# SML-230109PCB1__BLE.net
KiCad netlist of a schematic drawn in Altium Designer
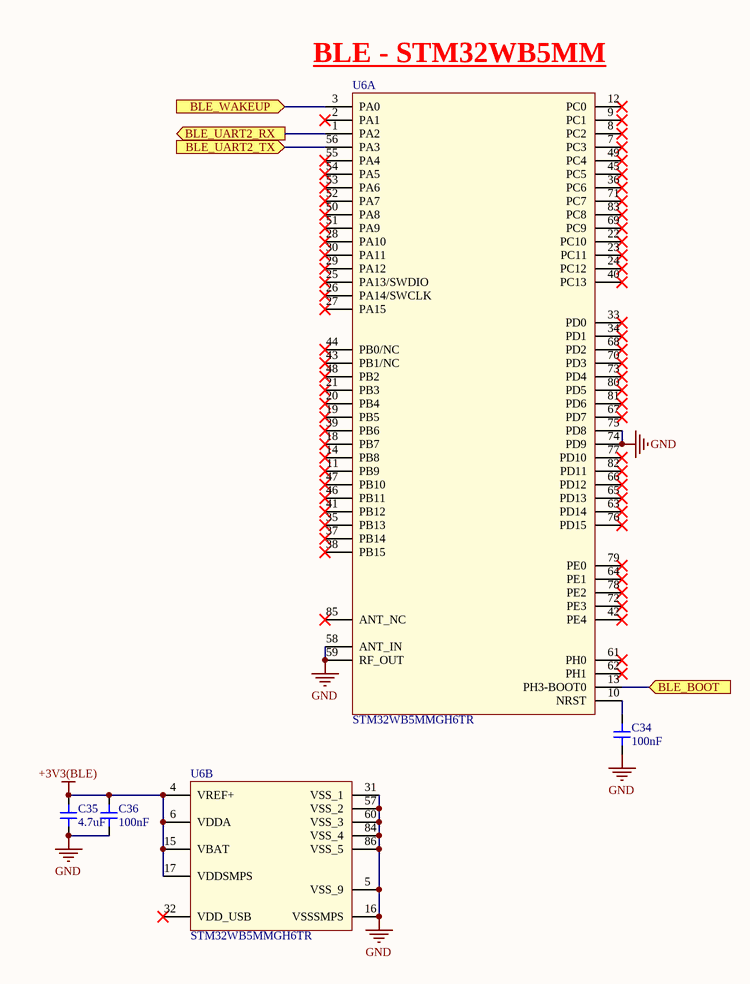
[diagram p0: SML-230109PCB1__BLE.SchDoc]

(export (version "E")
  (design (tool "Eeschema 10.0.6"))
  (components
    (comp (ref "C34")
      (value "100nF")
      (footprint "[G] CAP-MLCC__0603")
      (description "CAP MLCC 0603")
      (fields (field (name "VOLTAGE") "010") (field (name "Comment") "."))
      (libsource (lib "DEB_LIB_SCH_22-03") (part "CAP_MLCC_0603"))
    )
    (comp (ref "C35")
      (value "4.7uF")
      (footprint "[G] CAP-MLCC__0603")
      (description "CAP MLCC 0603")
      (fields (field (name "VOLTAGE") "010") (field (name "Comment") "."))
      (libsource (lib "DEB_LIB_SCH_22-03") (part "CAP_MLCC_0603"))
    )
    (comp (ref "C36")
      (value "100nF")
      (footprint "[G] CAP-MLCC__0603")
      (description "CAP MLCC 0603")
      (fields (field (name "VOLTAGE") "010") (field (name "Comment") "."))
      (libsource (lib "DEB_LIB_SCH_22-03") (part "CAP_MLCC_0603"))
    )
    (comp (ref "U6")
      (value ".")
      (footprint "MCU/BLE__STM32WB5MMG__SIP-LGA-86")
      (description "MCU/BLE ARM 32bit, M0+ & M4 (64MHz), 1MB/256KB, 6dBm, -96dBm, SIP-LGA-86")
      (fields (field (name "[01] - MPN CODE") "STM32WB5MMGH6TR"))
      (libsource (lib "DEB_LIB_SCH_22-03") (part "STM32WB5MMGH6TR"))
    )
  )
  (nets
    (net (code "1") (name "+3V3(BLE)") (class "Default")
      (node (ref "C35") (pin "2") (pinfunction "2_2") (pintype "passive"))
      (node (ref "C36") (pin "2") (pinfunction "2_2") (pintype "passive"))
      (node (ref "U6") (pin "15") (pinfunction "VBAT_15") (pintype "passive"))
      (node (ref "U6") (pin "17") (pinfunction "VDDSMPS_17") (pintype "passive"))
      (node (ref "U6") (pin "4") (pinfunction "VREF+_4") (pintype "passive"))
      (node (ref "U6") (pin "6") (pinfunction "VDDA_6") (pintype "passive"))
    )
    (net (code "2") (name "/BLE_BOOT") (class "Default")
      (node (ref "U6") (pin "13") (pinfunction "PH3-BOOT0_13") (pintype "passive"))
    )
    (net (code "3") (name "/BLE_UART2_RX") (class "Default")
      (node (ref "U6") (pin "1") (pinfunction "PA2_1") (pintype "passive"))
    )
    (net (code "4") (name "/BLE_UART2_TX") (class "Default")
      (node (ref "U6") (pin "56") (pinfunction "PA3_56") (pintype "passive"))
    )
    (net (code "5") (name "/BLE_WAKEUP") (class "Default")
      (node (ref "U6") (pin "3") (pinfunction "PA0_3") (pintype "passive"))
    )
    (net (code "6") (name "GND") (class "Default")
      (node (ref "C34") (pin "1") (pinfunction "1_1") (pintype "passive"))
      (node (ref "C35") (pin "1") (pinfunction "1_1") (pintype "passive"))
      (node (ref "C36") (pin "1") (pinfunction "1_1") (pintype "passive"))
      (node (ref "U6") (pin "16") (pinfunction "VSSSMPS_16") (pintype "passive"))
      (node (ref "U6") (pin "31") (pinfunction "VSS_1_31") (pintype "passive"))
      (node (ref "U6") (pin "5") (pinfunction "VSS_9_5") (pintype "passive"))
      (node (ref "U6") (pin "57") (pinfunction "VSS_2_57") (pintype "passive"))
      (node (ref "U6") (pin "58") (pinfunction "ANT_IN_58") (pintype "passive"))
      (node (ref "U6") (pin "59") (pinfunction "RF_OUT_59") (pintype "passive"))
      (node (ref "U6") (pin "60") (pinfunction "VSS_3_60") (pintype "passive"))
      (node (ref "U6") (pin "74") (pinfunction "PD9_74") (pintype "passive"))
      (node (ref "U6") (pin "75") (pinfunction "PD8_75") (pintype "passive"))
      (node (ref "U6") (pin "84") (pinfunction "VSS_4_84") (pintype "passive"))
      (node (ref "U6") (pin "86") (pinfunction "VSS_5_86") (pintype "passive"))
    )
    (net (code "7") (name "Net-(U6A-NRST)") (class "Default")
      (node (ref "C34") (pin "2") (pinfunction "2_2") (pintype "passive"))
      (node (ref "U6") (pin "10") (pinfunction "NRST_10") (pintype "passive"))
    )
    (net (code "8") (name "unconnected-(U6A-ANT_NC-Pad85)") (class "Default")
      (node (ref "U6") (pin "85") (pinfunction "ANT_NC_85") (pintype "passive+no_connect"))
    )
    (net (code "9") (name "unconnected-(U6A-PA1-Pad2)") (class "Default")
      (node (ref "U6") (pin "2") (pinfunction "PA1_2") (pintype "passive+no_connect"))
    )
    (net (code "10") (name "unconnected-(U6A-PA4-Pad55)") (class "Default")
      (node (ref "U6") (pin "55") (pinfunction "PA4_55") (pintype "passive+no_connect"))
    )
    (net (code "11") (name "unconnected-(U6A-PA5-Pad54)") (class "Default")
      (node (ref "U6") (pin "54") (pinfunction "PA5_54") (pintype "passive+no_connect"))
    )
    (net (code "12") (name "unconnected-(U6A-PA6-Pad53)") (class "Default")
      (node (ref "U6") (pin "53") (pinfunction "PA6_53") (pintype "passive+no_connect"))
    )
    (net (code "13") (name "unconnected-(U6A-PA7-Pad52)") (class "Default")
      (node (ref "U6") (pin "52") (pinfunction "PA7_52") (pintype "passive+no_connect"))
    )
    (net (code "14") (name "unconnected-(U6A-PA8-Pad50)") (class "Default")
      (node (ref "U6") (pin "50") (pinfunction "PA8_50") (pintype "passive+no_connect"))
    )
    (net (code "15") (name "unconnected-(U6A-PA9-Pad51)") (class "Default")
      (node (ref "U6") (pin "51") (pinfunction "PA9_51") (pintype "passive+no_connect"))
    )
    (net (code "16") (name "unconnected-(U6A-PA10-Pad28)") (class "Default")
      (node (ref "U6") (pin "28") (pinfunction "PA10_28") (pintype "passive+no_connect"))
    )
    (net (code "17") (name "unconnected-(U6A-PA11-Pad30)") (class "Default")
      (node (ref "U6") (pin "30") (pinfunction "PA11_30") (pintype "passive+no_connect"))
    )
    (net (code "18") (name "unconnected-(U6A-PA12-Pad29)") (class "Default")
      (node (ref "U6") (pin "29") (pinfunction "PA12_29") (pintype "passive+no_connect"))
    )
    (net (code "19") (name "unconnected-(U6A-PA13{slash}SWDIO-Pad25)") (class "Default")
      (node (ref "U6") (pin "25") (pinfunction "PA13/SWDIO_25") (pintype "passive+no_connect"))
    )
    (net (code "20") (name "unconnected-(U6A-PA14{slash}SWCLK-Pad26)") (class "Default")
      (node (ref "U6") (pin "26") (pinfunction "PA14/SWCLK_26") (pintype "passive+no_connect"))
    )
    (net (code "21") (name "unconnected-(U6A-PA15-Pad27)") (class "Default")
      (node (ref "U6") (pin "27") (pinfunction "PA15_27") (pintype "passive+no_connect"))
    )
    (net (code "22") (name "unconnected-(U6A-PB0{slash}NC-Pad44)") (class "Default")
      (node (ref "U6") (pin "44") (pinfunction "PB0/NC_44") (pintype "passive+no_connect"))
    )
    (net (code "23") (name "unconnected-(U6A-PB1{slash}NC-Pad43)") (class "Default")
      (node (ref "U6") (pin "43") (pinfunction "PB1/NC_43") (pintype "passive+no_connect"))
    )
    (net (code "24") (name "unconnected-(U6A-PB2-Pad48)") (class "Default")
      (node (ref "U6") (pin "48") (pinfunction "PB2_48") (pintype "passive+no_connect"))
    )
    (net (code "25") (name "unconnected-(U6A-PB3-Pad21)") (class "Default")
      (node (ref "U6") (pin "21") (pinfunction "PB3_21") (pintype "passive+no_connect"))
    )
    (net (code "26") (name "unconnected-(U6A-PB4-Pad20)") (class "Default")
      (node (ref "U6") (pin "20") (pinfunction "PB4_20") (pintype "passive+no_connect"))
    )
    (net (code "27") (name "unconnected-(U6A-PB5-Pad19)") (class "Default")
      (node (ref "U6") (pin "19") (pinfunction "PB5_19") (pintype "passive+no_connect"))
    )
    (net (code "28") (name "unconnected-(U6A-PB6-Pad39)") (class "Default")
      (node (ref "U6") (pin "39") (pinfunction "PB6_39") (pintype "passive+no_connect"))
    )
    (net (code "29") (name "unconnected-(U6A-PB7-Pad18)") (class "Default")
      (node (ref "U6") (pin "18") (pinfunction "PB7_18") (pintype "passive+no_connect"))
    )
    (net (code "30") (name "unconnected-(U6A-PB8-Pad14)") (class "Default")
      (node (ref "U6") (pin "14") (pinfunction "PB8_14") (pintype "passive+no_connect"))
    )
    (net (code "31") (name "unconnected-(U6A-PB9-Pad11)") (class "Default")
      (node (ref "U6") (pin "11") (pinfunction "PB9_11") (pintype "passive+no_connect"))
    )
    (net (code "32") (name "unconnected-(U6A-PB10-Pad47)") (class "Default")
      (node (ref "U6") (pin "47") (pinfunction "PB10_47") (pintype "passive+no_connect"))
    )
    (net (code "33") (name "unconnected-(U6A-PB11-Pad46)") (class "Default")
      (node (ref "U6") (pin "46") (pinfunction "PB11_46") (pintype "passive+no_connect"))
    )
    (net (code "34") (name "unconnected-(U6A-PB12-Pad41)") (class "Default")
      (node (ref "U6") (pin "41") (pinfunction "PB12_41") (pintype "passive+no_connect"))
    )
    (net (code "35") (name "unconnected-(U6A-PB13-Pad35)") (class "Default")
      (node (ref "U6") (pin "35") (pinfunction "PB13_35") (pintype "passive+no_connect"))
    )
    (net (code "36") (name "unconnected-(U6A-PB14-Pad37)") (class "Default")
      (node (ref "U6") (pin "37") (pinfunction "PB14_37") (pintype "passive+no_connect"))
    )
    (net (code "37") (name "unconnected-(U6A-PB15-Pad38)") (class "Default")
      (node (ref "U6") (pin "38") (pinfunction "PB15_38") (pintype "passive+no_connect"))
    )
    (net (code "38") (name "unconnected-(U6A-PC0-Pad12)") (class "Default")
      (node (ref "U6") (pin "12") (pinfunction "PC0_12") (pintype "passive+no_connect"))
    )
    (net (code "39") (name "unconnected-(U6A-PC1-Pad9)") (class "Default")
      (node (ref "U6") (pin "9") (pinfunction "PC1_9") (pintype "passive+no_connect"))
    )
    (net (code "40") (name "unconnected-(U6A-PC2-Pad8)") (class "Default")
      (node (ref "U6") (pin "8") (pinfunction "PC2_8") (pintype "passive+no_connect"))
    )
    (net (code "41") (name "unconnected-(U6A-PC3-Pad7)") (class "Default")
      (node (ref "U6") (pin "7") (pinfunction "PC3_7") (pintype "passive+no_connect"))
    )
    (net (code "42") (name "unconnected-(U6A-PC4-Pad49)") (class "Default")
      (node (ref "U6") (pin "49") (pinfunction "PC4_49") (pintype "passive+no_connect"))
    )
    (net (code "43") (name "unconnected-(U6A-PC5-Pad45)") (class "Default")
      (node (ref "U6") (pin "45") (pinfunction "PC5_45") (pintype "passive+no_connect"))
    )
    (net (code "44") (name "unconnected-(U6A-PC6-Pad36)") (class "Default")
      (node (ref "U6") (pin "36") (pinfunction "PC6_36") (pintype "passive+no_connect"))
    )
    (net (code "45") (name "unconnected-(U6A-PC7-Pad71)") (class "Default")
      (node (ref "U6") (pin "71") (pinfunction "PC7_71") (pintype "passive+no_connect"))
    )
    (net (code "46") (name "unconnected-(U6A-PC8-Pad83)") (class "Default")
      (node (ref "U6") (pin "83") (pinfunction "PC8_83") (pintype "passive+no_connect"))
    )
    (net (code "47") (name "unconnected-(U6A-PC9-Pad69)") (class "Default")
      (node (ref "U6") (pin "69") (pinfunction "PC9_69") (pintype "passive+no_connect"))
    )
    (net (code "48") (name "unconnected-(U6A-PC10-Pad22)") (class "Default")
      (node (ref "U6") (pin "22") (pinfunction "PC10_22") (pintype "passive+no_connect"))
    )
    (net (code "49") (name "unconnected-(U6A-PC11-Pad23)") (class "Default")
      (node (ref "U6") (pin "23") (pinfunction "PC11_23") (pintype "passive+no_connect"))
    )
    (net (code "50") (name "unconnected-(U6A-PC12-Pad24)") (class "Default")
      (node (ref "U6") (pin "24") (pinfunction "PC12_24") (pintype "passive+no_connect"))
    )
    (net (code "51") (name "unconnected-(U6A-PC13-Pad40)") (class "Default")
      (node (ref "U6") (pin "40") (pinfunction "PC13_40") (pintype "passive+no_connect"))
    )
    (net (code "52") (name "unconnected-(U6A-PD0-Pad33)") (class "Default")
      (node (ref "U6") (pin "33") (pinfunction "PD0_33") (pintype "passive+no_connect"))
    )
    (net (code "53") (name "unconnected-(U6A-PD1-Pad34)") (class "Default")
      (node (ref "U6") (pin "34") (pinfunction "PD1_34") (pintype "passive+no_connect"))
    )
    (net (code "54") (name "unconnected-(U6A-PD2-Pad68)") (class "Default")
      (node (ref "U6") (pin "68") (pinfunction "PD2_68") (pintype "passive+no_connect"))
    )
    (net (code "55") (name "unconnected-(U6A-PD3-Pad70)") (class "Default")
      (node (ref "U6") (pin "70") (pinfunction "PD3_70") (pintype "passive+no_connect"))
    )
    (net (code "56") (name "unconnected-(U6A-PD4-Pad73)") (class "Default")
      (node (ref "U6") (pin "73") (pinfunction "PD4_73") (pintype "passive+no_connect"))
    )
    (net (code "57") (name "unconnected-(U6A-PD5-Pad80)") (class "Default")
      (node (ref "U6") (pin "80") (pinfunction "PD5_80") (pintype "passive+no_connect"))
    )
    (net (code "58") (name "unconnected-(U6A-PD6-Pad81)") (class "Default")
      (node (ref "U6") (pin "81") (pinfunction "PD6_81") (pintype "passive+no_connect"))
    )
    (net (code "59") (name "unconnected-(U6A-PD7-Pad67)") (class "Default")
      (node (ref "U6") (pin "67") (pinfunction "PD7_67") (pintype "passive+no_connect"))
    )
    (net (code "60") (name "unconnected-(U6A-PD10-Pad77)") (class "Default")
      (node (ref "U6") (pin "77") (pinfunction "PD10_77") (pintype "passive+no_connect"))
    )
    (net (code "61") (name "unconnected-(U6A-PD11-Pad82)") (class "Default")
      (node (ref "U6") (pin "82") (pinfunction "PD11_82") (pintype "passive+no_connect"))
    )
    (net (code "62") (name "unconnected-(U6A-PD12-Pad66)") (class "Default")
      (node (ref "U6") (pin "66") (pinfunction "PD12_66") (pintype "passive+no_connect"))
    )
    (net (code "63") (name "unconnected-(U6A-PD13-Pad65)") (class "Default")
      (node (ref "U6") (pin "65") (pinfunction "PD13_65") (pintype "passive+no_connect"))
    )
    (net (code "64") (name "unconnected-(U6A-PD14-Pad63)") (class "Default")
      (node (ref "U6") (pin "63") (pinfunction "PD14_63") (pintype "passive+no_connect"))
    )
    (net (code "65") (name "unconnected-(U6A-PD15-Pad76)") (class "Default")
      (node (ref "U6") (pin "76") (pinfunction "PD15_76") (pintype "passive+no_connect"))
    )
    (net (code "66") (name "unconnected-(U6A-PE0-Pad79)") (class "Default")
      (node (ref "U6") (pin "79") (pinfunction "PE0_79") (pintype "passive+no_connect"))
    )
    (net (code "67") (name "unconnected-(U6A-PE1-Pad64)") (class "Default")
      (node (ref "U6") (pin "64") (pinfunction "PE1_64") (pintype "passive+no_connect"))
    )
    (net (code "68") (name "unconnected-(U6A-PE2-Pad78)") (class "Default")
      (node (ref "U6") (pin "78") (pinfunction "PE2_78") (pintype "passive+no_connect"))
    )
    (net (code "69") (name "unconnected-(U6A-PE3-Pad72)") (class "Default")
      (node (ref "U6") (pin "72") (pinfunction "PE3_72") (pintype "passive+no_connect"))
    )
    (net (code "70") (name "unconnected-(U6A-PE4-Pad42)") (class "Default")
      (node (ref "U6") (pin "42") (pinfunction "PE4_42") (pintype "passive+no_connect"))
    )
    (net (code "71") (name "unconnected-(U6A-PH0-Pad61)") (class "Default")
      (node (ref "U6") (pin "61") (pinfunction "PH0_61") (pintype "passive+no_connect"))
    )
    (net (code "72") (name "unconnected-(U6A-PH1-Pad62)") (class "Default")
      (node (ref "U6") (pin "62") (pinfunction "PH1_62") (pintype "passive+no_connect"))
    )
    (net (code "73") (name "unconnected-(U6B-VDD_USB-Pad32)") (class "Default")
      (node (ref "U6") (pin "32") (pinfunction "VDD_USB_32") (pintype "passive+no_connect"))
    )
  )
)
